# kasianov_repiter_a.net
KiCad netlist of a schematic drawn in EasyEDA
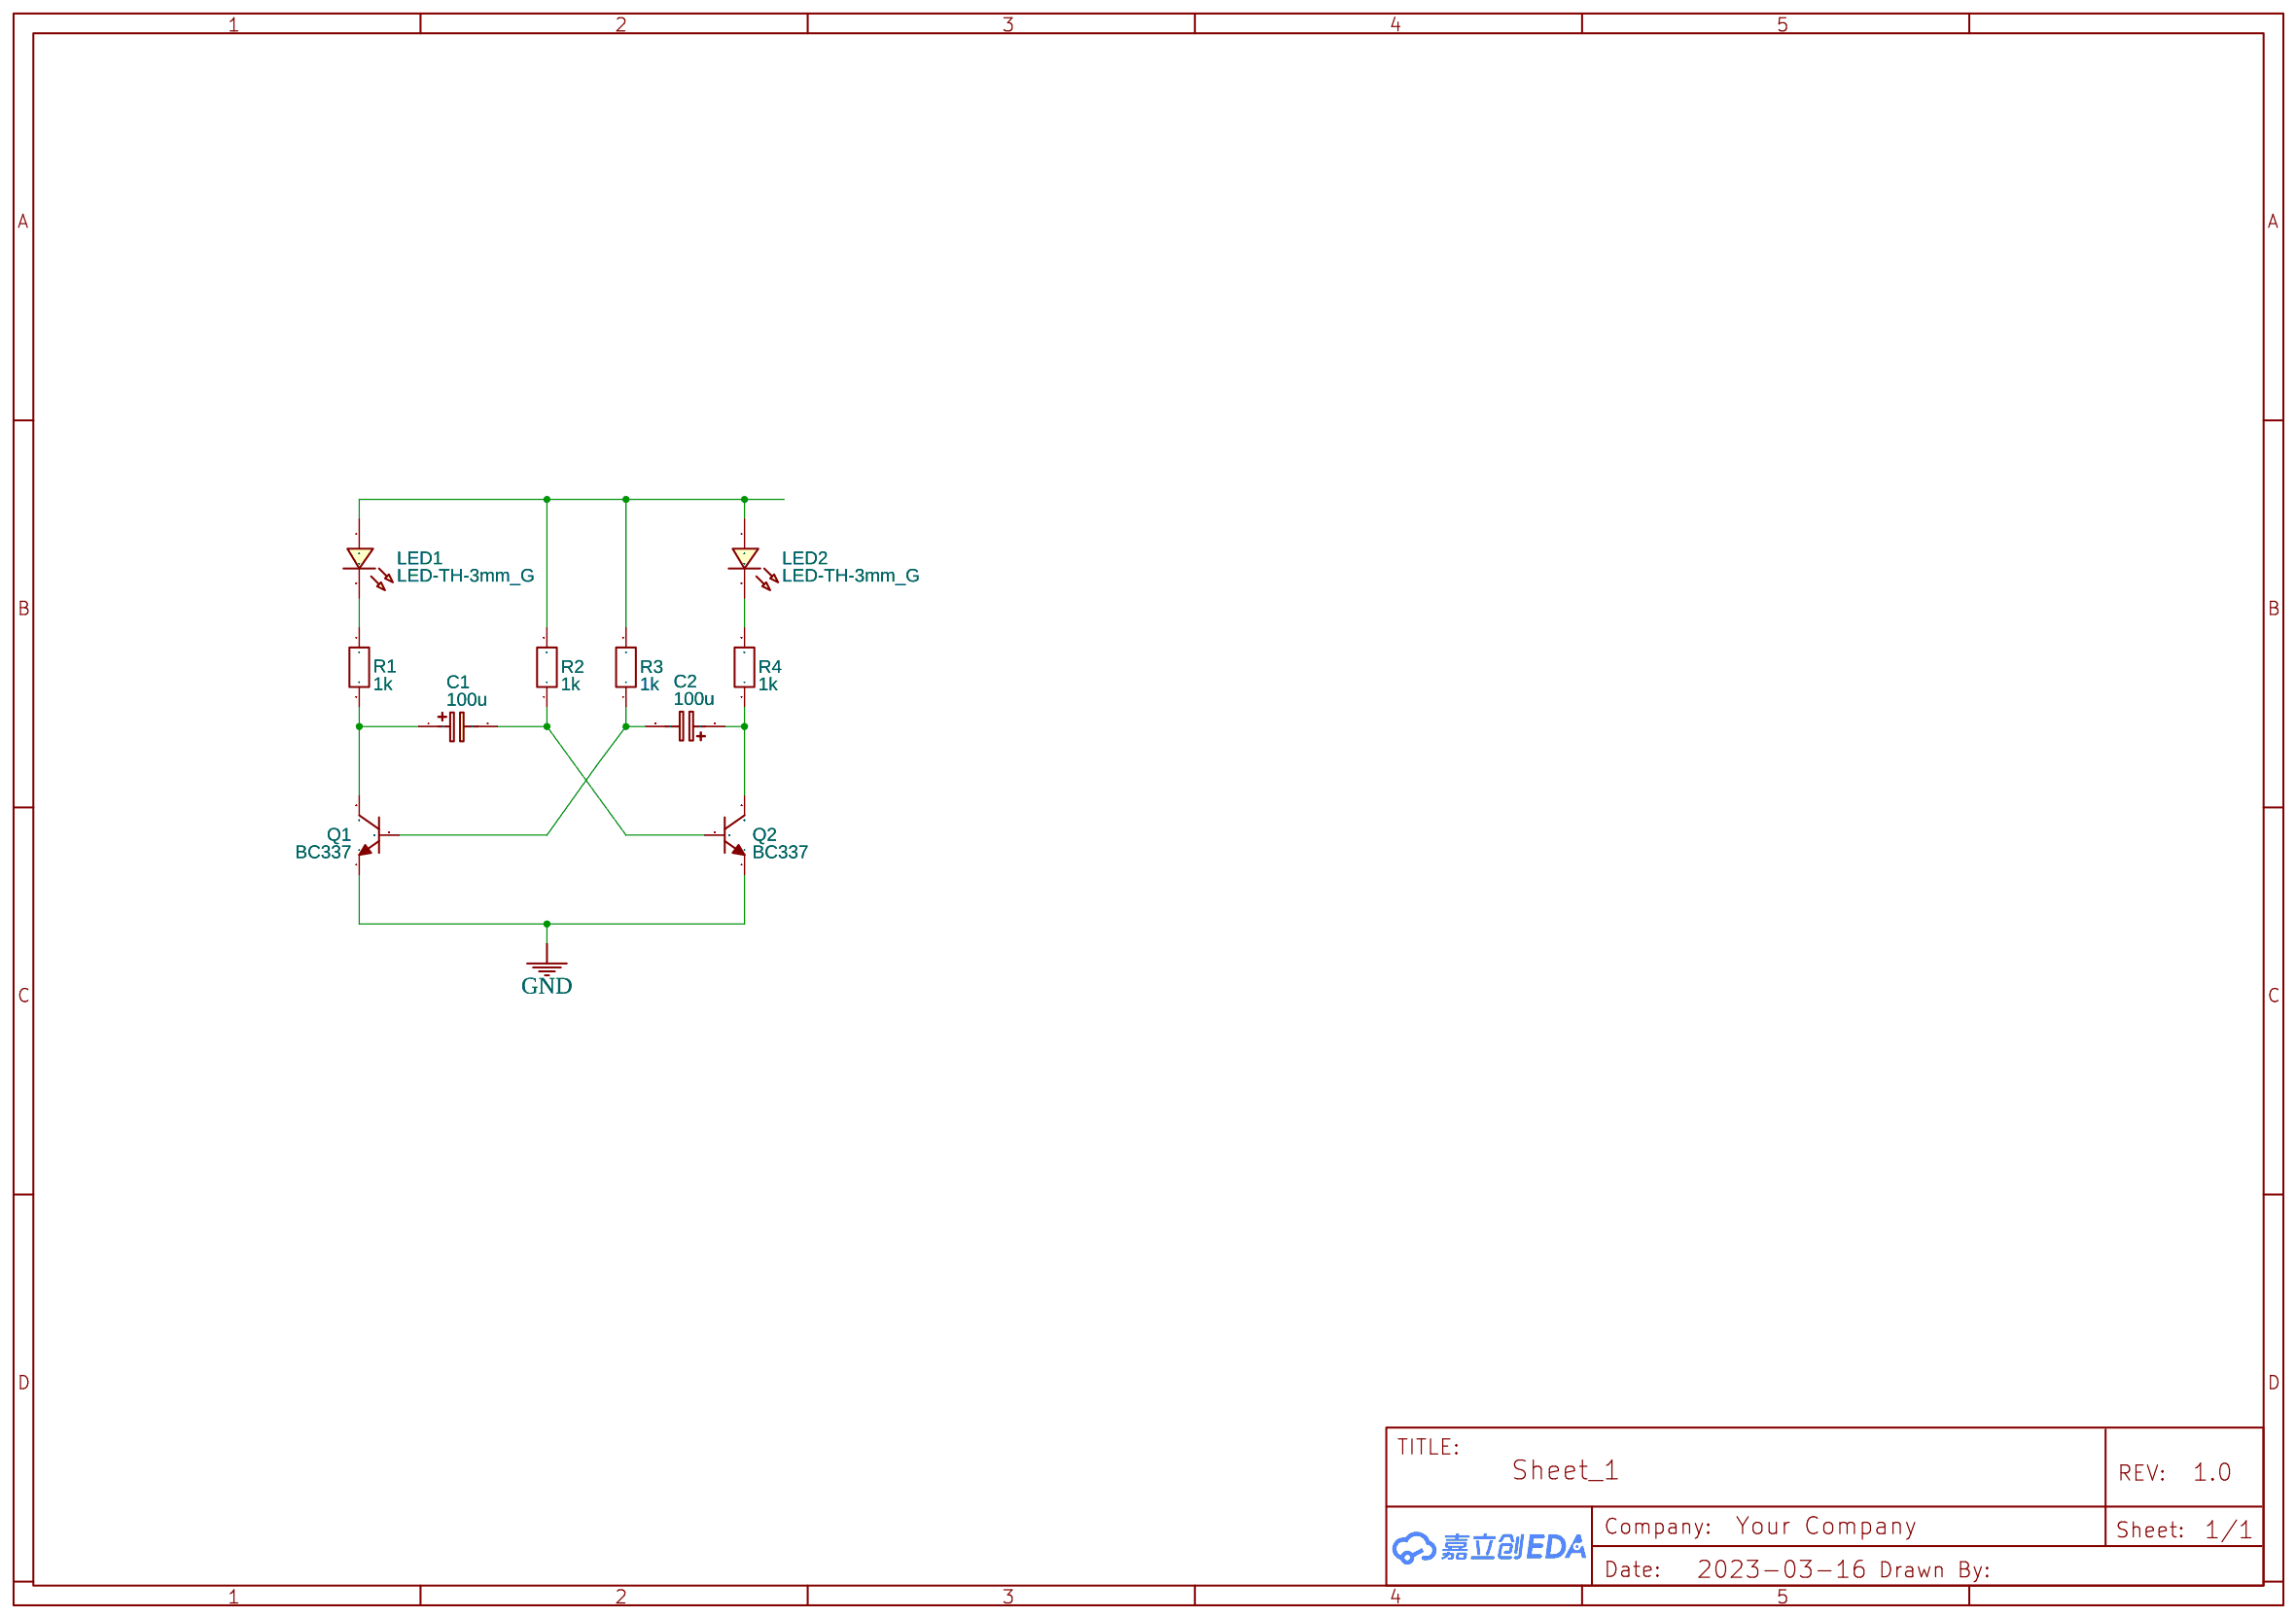
[diagram p0: schematic sheet]

(export (version "E")
  (design (tool "Eeschema 10.0.6"))
  (components
    (comp (ref "C1") (value "100u") (libsource (lib "") (part "C_Tan_SMD_A_EU_1")))
    (comp (ref "C2") (value "100u") (libsource (lib "") (part "C_Tan_SMD_A_EU")))
    (comp (ref "LED1")
      (value "LED-TH-3mm_G")
      (fields
        (field (name "BOM_Manufacturer Part") "204-10SYGD/S530-E3")
        (field (name "BOM_Supplier Part") "C85161")
      )
      (libsource (lib "") (part "LED-TH-3mm_G"))
    )
    (comp (ref "LED2")
      (value "LED-TH-3mm_G")
      (fields
        (field (name "BOM_Manufacturer Part") "204-10SYGD/S530-E3")
        (field (name "BOM_Supplier Part") "C85161")
      )
      (libsource (lib "") (part "LED-TH-3mm_G"))
    )
    (comp (ref "Q1")
      (value "BC337")
      (fields (field (name "BOM_Manufacturer Part") "2N3904") (field (name "BOM_Supplier Part") "C118538"))
      (libsource (lib "") (part "2N3904(TO-92)"))
    )
    (comp (ref "Q2")
      (value "BC337")
      (fields (field (name "BOM_Manufacturer Part") "2N3904") (field (name "BOM_Supplier Part") "C118538"))
      (libsource (lib "") (part "2N3904(TO-92)_1"))
    )
    (comp (ref "R1") (value "1k") (libsource (lib "") (part "R_0603_EU_1")))
    (comp (ref "R2") (value "1k") (libsource (lib "") (part "R_0603_EU")))
    (comp (ref "R3") (value "1k") (libsource (lib "") (part "R_0603_EU")))
    (comp (ref "R4") (value "1k") (libsource (lib "") (part "R_0603_EU")))
  )
  (nets
    (net (code "1") (name "GND") (class "Default")
      (node (ref "Q1") (pin "1") (pinfunction "E_1") (pintype "unspecified"))
      (node (ref "Q2") (pin "1") (pinfunction "E_1") (pintype "unspecified"))
    )
    (net (code "2") (name "Net-(LED1-Pad1)") (class "Default")
      (node (ref "LED1") (pin "1") (pinfunction "1_1") (pintype "unspecified"))
      (node (ref "LED2") (pin "1") (pinfunction "1_1") (pintype "unspecified"))
      (node (ref "R2") (pin "2") (pinfunction "2_2") (pintype "unspecified"))
      (node (ref "R3") (pin "2") (pinfunction "2_2") (pintype "unspecified"))
    )
    (net (code "3") (name "Net-(LED1-Pad2)") (class "Default")
      (node (ref "LED1") (pin "2") (pinfunction "2_2") (pintype "unspecified"))
      (node (ref "R1") (pin "1") (pinfunction "1_1") (pintype "unspecified"))
    )
    (net (code "4") (name "Net-(LED2-Pad2)") (class "Default")
      (node (ref "LED2") (pin "2") (pinfunction "2_2") (pintype "unspecified"))
      (node (ref "R4") (pin "2") (pinfunction "2_2") (pintype "unspecified"))
    )
    (net (code "5") (name "Net-(Q1-B)") (class "Default")
      (node (ref "C2") (pin "2") (pinfunction "2_2") (pintype "unspecified"))
      (node (ref "Q1") (pin "2") (pinfunction "B_2") (pintype "unspecified"))
      (node (ref "R3") (pin "1") (pinfunction "1_1") (pintype "unspecified"))
    )
    (net (code "6") (name "Net-(Q1-C)") (class "Default")
      (node (ref "C1") (pin "1") (pinfunction "1_1") (pintype "unspecified"))
      (node (ref "Q1") (pin "3") (pinfunction "C_3") (pintype "unspecified"))
      (node (ref "R1") (pin "2") (pinfunction "2_2") (pintype "unspecified"))
    )
    (net (code "7") (name "Net-(Q2-B)") (class "Default")
      (node (ref "C1") (pin "2") (pinfunction "2_2") (pintype "unspecified"))
      (node (ref "Q2") (pin "2") (pinfunction "B_2") (pintype "unspecified"))
      (node (ref "R2") (pin "1") (pinfunction "1_1") (pintype "unspecified"))
    )
    (net (code "8") (name "Net-(Q2-C)") (class "Default")
      (node (ref "C2") (pin "1") (pinfunction "1_1") (pintype "unspecified"))
      (node (ref "Q2") (pin "3") (pinfunction "C_3") (pintype "unspecified"))
      (node (ref "R4") (pin "1") (pinfunction "1_1") (pintype "unspecified"))
    )
  )
)
